# cardV3.net
KiCad netlist of a schematic drawn in EAGLE
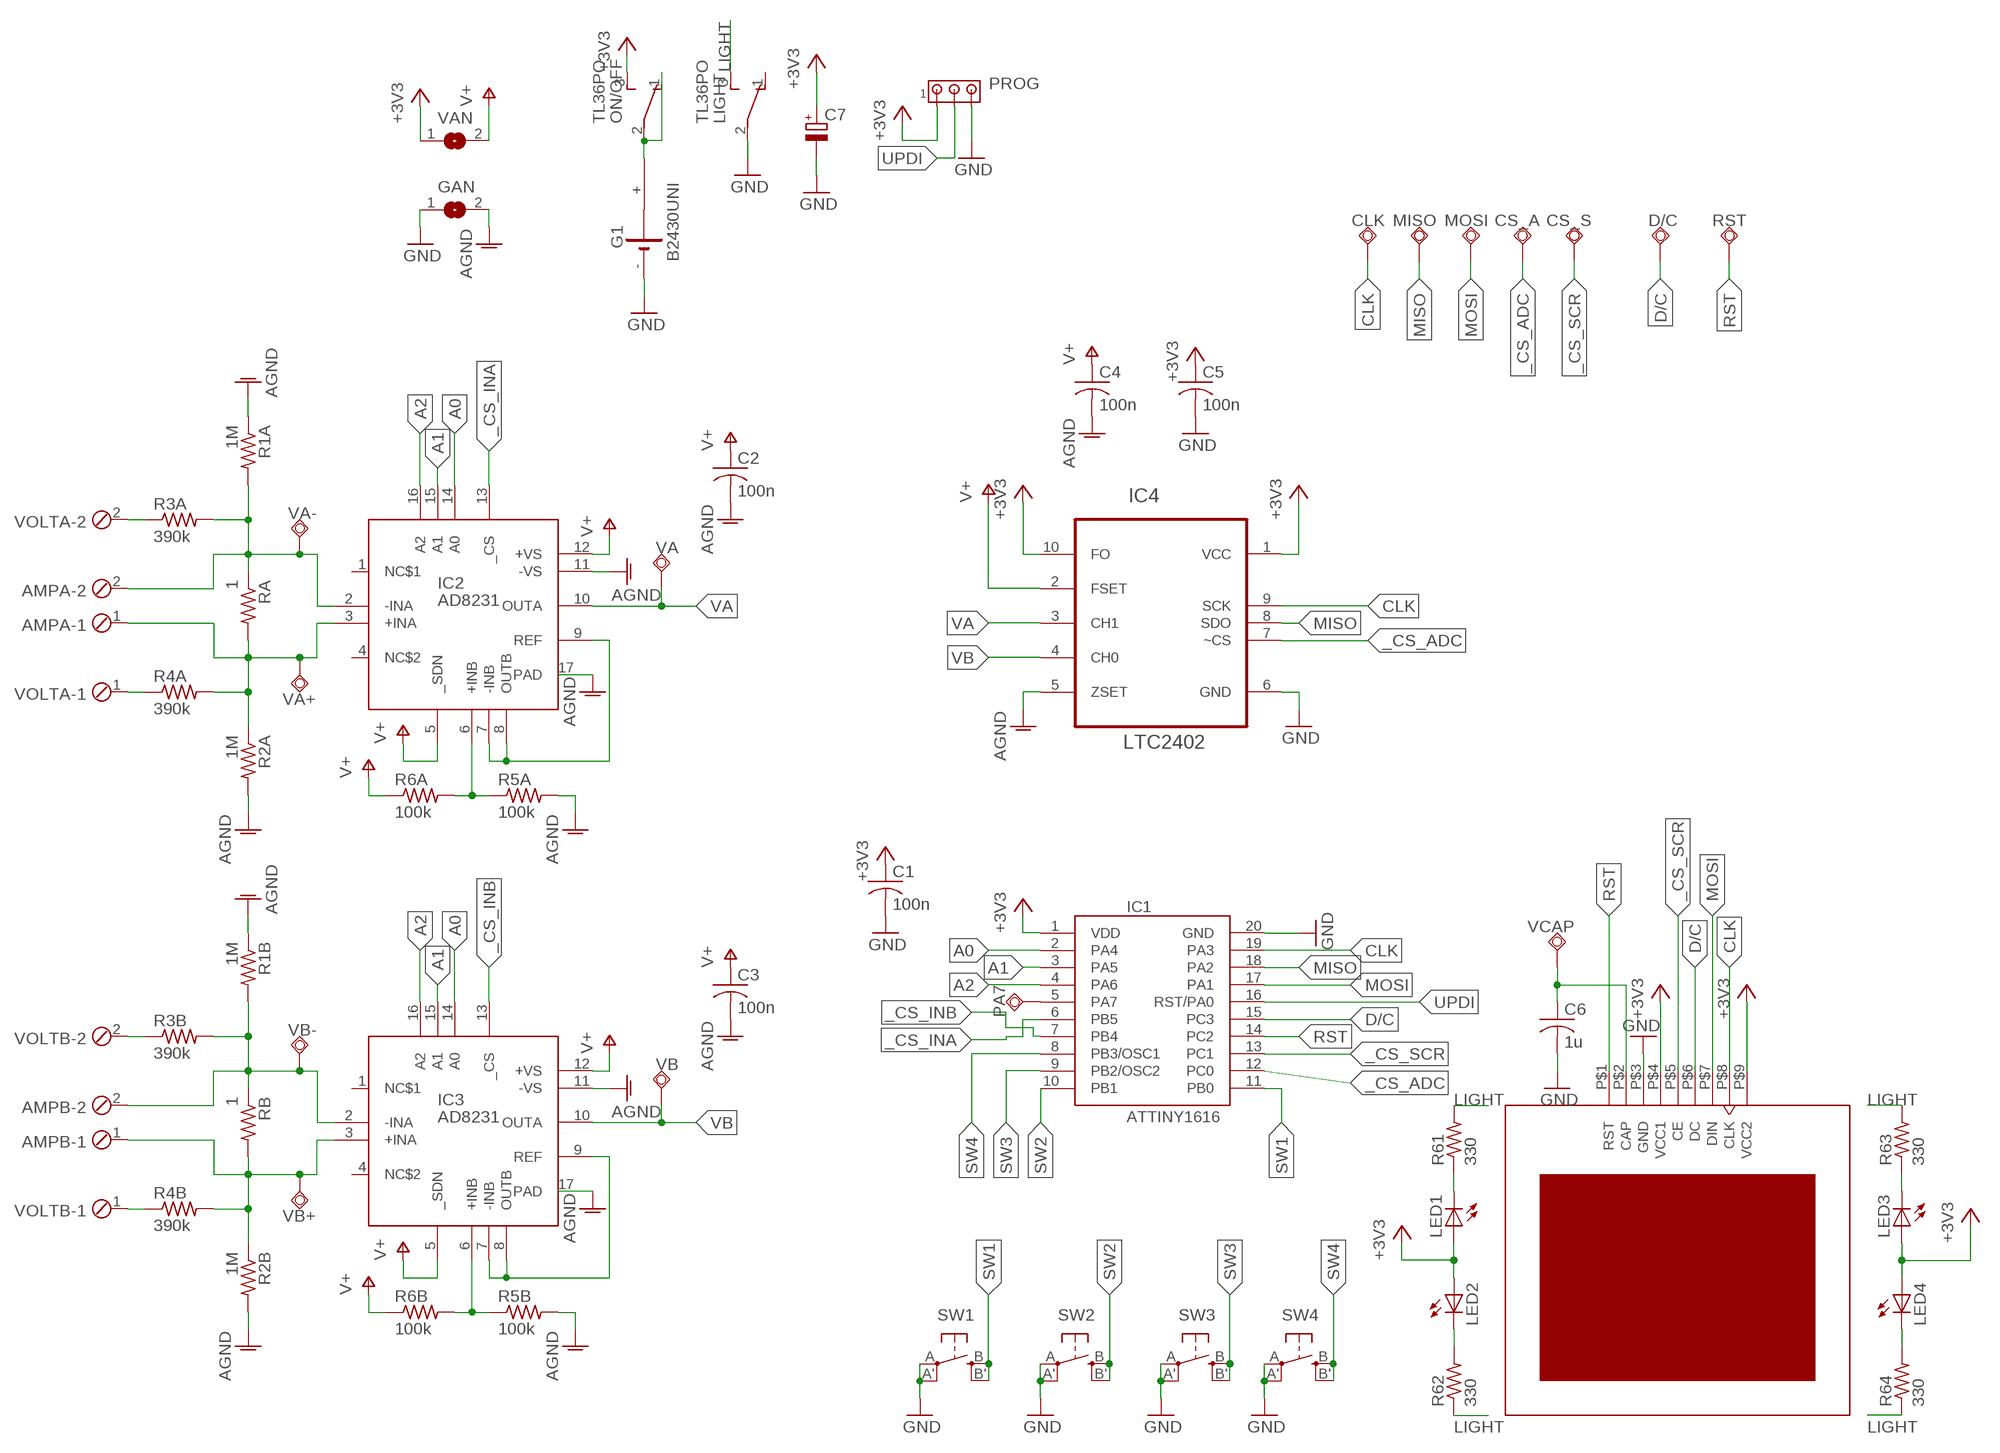
[diagram p0: schematic, sheet 1]

(export (version "E")
  (design (tool "Eeschema 10.0.6"))
  (components
    (comp (ref "AMPA")
      (value "MPT2")
      (footprint "eagle-import:2POL254")
      (libsource (lib "eagle-import") (part "MPT2"))
    )
    (comp (ref "AMPB")
      (value "MPT2")
      (footprint "eagle-import:2POL254")
      (libsource (lib "eagle-import") (part "MPT2"))
    )
    (comp (ref "C1")
      (value "100n")
      (footprint "eagle-import:C0805K")
      (libsource (lib "eagle-import") (part "C-USC0805K"))
    )
    (comp (ref "C2")
      (value "100n")
      (footprint "eagle-import:C0805K")
      (libsource (lib "eagle-import") (part "C-USC0805K"))
    )
    (comp (ref "C3")
      (value "100n")
      (footprint "eagle-import:C0805K")
      (libsource (lib "eagle-import") (part "C-USC0805K"))
    )
    (comp (ref "C4")
      (value "100n")
      (footprint "eagle-import:C0805K")
      (libsource (lib "eagle-import") (part "C-USC0805K"))
    )
    (comp (ref "C5")
      (value "100n")
      (footprint "eagle-import:C0805K")
      (libsource (lib "eagle-import") (part "C-USC0805K"))
    )
    (comp (ref "C6")
      (value "1u")
      (footprint "eagle-import:C0805")
      (libsource (lib "eagle-import") (part "resistor_C-USC0805"))
    )
    (comp (ref "C7")
      (value "CPOL-EU153CLV-0405")
      (footprint "eagle-import:153CLV-0405")
      (libsource (lib "eagle-import") (part "CPOL-EU153CLV-0405"))
    )
    (comp (ref "CLK")
      (value "TPSQB1,27")
      (footprint "eagle-import:B1,27")
      (libsource (lib "eagle-import") (part "TPSQB1,27"))
    )
    (comp (ref "CS_A")
      (value "TPSQB1,27")
      (footprint "eagle-import:B1,27")
      (libsource (lib "eagle-import") (part "TPSQB1,27"))
    )
    (comp (ref "CS_S")
      (value "TPSQB1,27")
      (footprint "eagle-import:B1,27")
      (libsource (lib "eagle-import") (part "TPSQB1,27"))
    )
    (comp (ref "D/C")
      (value "TPSQB1,27")
      (footprint "eagle-import:B1,27")
      (libsource (lib "eagle-import") (part "TPSQB1,27"))
    )
    (comp (ref "G1")
      (value "B2430UNI")
      (footprint "eagle-import:B2430UNI")
      (libsource (lib "eagle-import") (part "B2430UNI"))
    )
    (comp (ref "GAN") (value "SJ") (footprint "eagle-import:SJ") (libsource (lib "eagle-import") (part "SJ")))
    (comp (ref "IC1")
      (value "ATTINY1616")
      (footprint "eagle-import:SO20W")
      (libsource (lib "eagle-import") (part "ATTINY1616"))
    )
    (comp (ref "IC2")
      (value "AD8231")
      (footprint "eagle-import:LFCSP16")
      (libsource (lib "eagle-import") (part "AD8231"))
    )
    (comp (ref "IC3")
      (value "AD8231")
      (footprint "eagle-import:LFCSP16")
      (libsource (lib "eagle-import") (part "AD8231"))
    )
    (comp (ref "IC4")
      (value "LTC2402")
      (footprint "eagle-import:MSOP10")
      (libsource (lib "eagle-import") (part "LTC2402CMS"))
    )
    (comp (ref "LED1")
      (value "LEDCHIP-LED0805")
      (footprint "eagle-import:CHIP-LED0805")
      (libsource (lib "eagle-import") (part "LEDCHIP-LED0805"))
    )
    (comp (ref "LED2")
      (value "LEDCHIP-LED0805")
      (footprint "eagle-import:CHIP-LED0805")
      (libsource (lib "eagle-import") (part "LEDCHIP-LED0805"))
    )
    (comp (ref "LED3")
      (value "LEDCHIP-LED0805")
      (footprint "eagle-import:CHIP-LED0805")
      (libsource (lib "eagle-import") (part "LEDCHIP-LED0805"))
    )
    (comp (ref "LED4")
      (value "LEDCHIP-LED0805")
      (footprint "eagle-import:CHIP-LED0805")
      (libsource (lib "eagle-import") (part "LEDCHIP-LED0805"))
    )
    (comp (ref "LIGHT")
      (value "TL36PO")
      (footprint "eagle-import:TL3XPO")
      (libsource (lib "eagle-import") (part "TL36PO"))
    )
    (comp (ref "MISO")
      (value "TPSQB1,27")
      (footprint "eagle-import:B1,27")
      (libsource (lib "eagle-import") (part "TPSQB1,27"))
    )
    (comp (ref "MOSI")
      (value "TPSQB1,27")
      (footprint "eagle-import:B1,27")
      (libsource (lib "eagle-import") (part "TPSQB1,27"))
    )
    (comp (ref "ON/OFF")
      (value "TL36PO")
      (footprint "eagle-import:TL3XPO")
      (libsource (lib "eagle-import") (part "TL36PO"))
    )
    (comp (ref "PA7")
      (value "TPSQB1,27")
      (footprint "eagle-import:B1,27")
      (libsource (lib "eagle-import") (part "TPSQB1,27"))
    )
    (comp (ref "PROG")
      (value "MTA03-100")
      (footprint "eagle-import:10X03MTA")
      (libsource (lib "eagle-import") (part "MTA03-100"))
    )
    (comp (ref "R1A")
      (value "1M")
      (footprint "eagle-import:M0805")
      (libsource (lib "eagle-import") (part "R-US_M0805"))
    )
    (comp (ref "R1B")
      (value "1M")
      (footprint "eagle-import:M0805")
      (libsource (lib "eagle-import") (part "R-US_M0805"))
    )
    (comp (ref "R2A")
      (value "1M")
      (footprint "eagle-import:M0805")
      (libsource (lib "eagle-import") (part "R-US_M0805"))
    )
    (comp (ref "R2B")
      (value "1M")
      (footprint "eagle-import:M0805")
      (libsource (lib "eagle-import") (part "R-US_M0805"))
    )
    (comp (ref "R3A")
      (value "390k")
      (footprint "eagle-import:M0805")
      (libsource (lib "eagle-import") (part "R-US_M0805"))
    )
    (comp (ref "R3B")
      (value "390k")
      (footprint "eagle-import:M0805")
      (libsource (lib "eagle-import") (part "R-US_M0805"))
    )
    (comp (ref "R4A")
      (value "390k")
      (footprint "eagle-import:M0805")
      (libsource (lib "eagle-import") (part "R-US_M0805"))
    )
    (comp (ref "R4B")
      (value "390k")
      (footprint "eagle-import:M0805")
      (libsource (lib "eagle-import") (part "R-US_M0805"))
    )
    (comp (ref "R5A")
      (value "100k")
      (footprint "eagle-import:M0805")
      (libsource (lib "eagle-import") (part "R-US_M0805"))
    )
    (comp (ref "R5B")
      (value "100k")
      (footprint "eagle-import:M0805")
      (libsource (lib "eagle-import") (part "R-US_M0805"))
    )
    (comp (ref "R6A")
      (value "100k")
      (footprint "eagle-import:M0805")
      (libsource (lib "eagle-import") (part "R-US_M0805"))
    )
    (comp (ref "R6B")
      (value "100k")
      (footprint "eagle-import:M0805")
      (libsource (lib "eagle-import") (part "R-US_M0805"))
    )
    (comp (ref "R61")
      (value "330")
      (footprint "eagle-import:M0805")
      (libsource (lib "eagle-import") (part "R-US_M0805"))
    )
    (comp (ref "R62")
      (value "330")
      (footprint "eagle-import:M0805")
      (libsource (lib "eagle-import") (part "R-US_M0805"))
    )
    (comp (ref "R63")
      (value "330")
      (footprint "eagle-import:M0805")
      (libsource (lib "eagle-import") (part "R-US_M0805"))
    )
    (comp (ref "R64")
      (value "330")
      (footprint "eagle-import:M0805")
      (libsource (lib "eagle-import") (part "R-US_M0805"))
    )
    (comp (ref "RA")
      (value "1")
      (footprint "eagle-import:M0805")
      (libsource (lib "eagle-import") (part "R-US_M0805"))
    )
    (comp (ref "RB")
      (value "1")
      (footprint "eagle-import:M0805")
      (libsource (lib "eagle-import") (part "R-US_M0805"))
    )
    (comp (ref "RST")
      (value "TPSQB1,27")
      (footprint "eagle-import:B1,27")
      (libsource (lib "eagle-import") (part "TPSQB1,27"))
    )
    (comp (ref "SCR")
      (value "NOKIA_SCREEN")
      (footprint "eagle-import:NOKIA_SCREEN")
      (libsource (lib "eagle-import") (part "NOKIA_SCREEN"))
    )
    (comp (ref "SW1")
      (value "SPST_TACT-EVQQ2")
      (footprint "eagle-import:EVQ-Q2")
      (libsource (lib "eagle-import") (part "SPST_TACT-EVQQ2"))
    )
    (comp (ref "SW2")
      (value "SPST_TACT-EVQQ2")
      (footprint "eagle-import:EVQ-Q2")
      (libsource (lib "eagle-import") (part "SPST_TACT-EVQQ2"))
    )
    (comp (ref "SW3")
      (value "SPST_TACT-EVQQ2")
      (footprint "eagle-import:EVQ-Q2")
      (libsource (lib "eagle-import") (part "SPST_TACT-EVQQ2"))
    )
    (comp (ref "SW4")
      (value "SPST_TACT-EVQQ2")
      (footprint "eagle-import:EVQ-Q2")
      (libsource (lib "eagle-import") (part "SPST_TACT-EVQQ2"))
    )
    (comp (ref "VA")
      (value "TPSQB1,27")
      (footprint "eagle-import:B1,27")
      (libsource (lib "eagle-import") (part "TPSQB1,27"))
    )
    (comp (ref "VA+")
      (value "TPSQB1,27")
      (footprint "eagle-import:B1,27")
      (libsource (lib "eagle-import") (part "TPSQB1,27"))
    )
    (comp (ref "VA-")
      (value "TPSQB1,27")
      (footprint "eagle-import:B1,27")
      (libsource (lib "eagle-import") (part "TPSQB1,27"))
    )
    (comp (ref "VAN") (value "SJ") (footprint "eagle-import:SJ") (libsource (lib "eagle-import") (part "SJ")))
    (comp (ref "VB")
      (value "TPSQB1,27")
      (footprint "eagle-import:B1,27")
      (libsource (lib "eagle-import") (part "TPSQB1,27"))
    )
    (comp (ref "VB+")
      (value "TPSQB1,27")
      (footprint "eagle-import:B1,27")
      (libsource (lib "eagle-import") (part "TPSQB1,27"))
    )
    (comp (ref "VB-")
      (value "TPSQB1,27")
      (footprint "eagle-import:B1,27")
      (libsource (lib "eagle-import") (part "TPSQB1,27"))
    )
    (comp (ref "VCAP")
      (value "TPSQB1,27")
      (footprint "eagle-import:B1,27")
      (libsource (lib "eagle-import") (part "TPSQB1,27"))
    )
    (comp (ref "VOLTA")
      (value "MPT2")
      (footprint "eagle-import:2POL254")
      (libsource (lib "eagle-import") (part "MPT2"))
    )
    (comp (ref "VOLTB")
      (value "MPT2")
      (footprint "eagle-import:2POL254")
      (libsource (lib "eagle-import") (part "MPT2"))
    )
  )
  (nets
    (net (code "1") (name "+3V3") (class "Default")
      (node (ref "C1") (pin "1") (pinfunction "1_1") (pintype "passive"))
      (node (ref "C5") (pin "1") (pinfunction "1_1") (pintype "passive"))
      (node (ref "C7") (pin "+") (pinfunction "+_+") (pintype "passive"))
      (node (ref "IC1") (pin "1") (pinfunction "VDD_1") (pintype "power_in"))
      (node (ref "IC4") (pin "1") (pinfunction "VCC_1") (pintype "power_in"))
      (node (ref "IC4") (pin "10") (pinfunction "FO_10") (pintype "input"))
      (node (ref "LED1") (pin "A") (pinfunction "A_A") (pintype "passive"))
      (node (ref "LED2") (pin "A") (pinfunction "A_A") (pintype "passive"))
      (node (ref "LED3") (pin "A") (pinfunction "A_A") (pintype "passive"))
      (node (ref "LED4") (pin "A") (pinfunction "A_A") (pintype "passive"))
      (node (ref "ON/OFF") (pin "3") (pinfunction "S_3") (pintype "passive"))
      (node (ref "PROG") (pin "1") (pinfunction "1_1") (pintype "passive"))
      (node (ref "SCR") (pin "P$4") (pinfunction "VCC1_P$4") (pintype "power_in"))
      (node (ref "SCR") (pin "P$9") (pinfunction "VCC2_P$9") (pintype "power_in"))
      (node (ref "VAN") (pin "1") (pinfunction "1_1") (pintype "passive"))
    )
    (net (code "2") (name "/LIGHT") (class "Default")
      (node (ref "LIGHT") (pin "3") (pinfunction "S_3") (pintype "passive"))
      (node (ref "R61") (pin "2") (pinfunction "2_2") (pintype "passive"))
      (node (ref "R62") (pin "1") (pinfunction "1_1") (pintype "passive"))
      (node (ref "R63") (pin "2") (pinfunction "2_2") (pintype "passive"))
      (node (ref "R64") (pin "1") (pinfunction "1_1") (pintype "passive"))
    )
    (net (code "3") (name "A0") (class "Default")
      (node (ref "IC1") (pin "2") (pinfunction "PA4_2") (pintype "bidirectional"))
      (node (ref "IC2") (pin "14") (pinfunction "A0_14") (pintype "input"))
      (node (ref "IC3") (pin "14") (pinfunction "A0_14") (pintype "input"))
    )
    (net (code "4") (name "A1") (class "Default")
      (node (ref "IC1") (pin "3") (pinfunction "PA5_3") (pintype "bidirectional"))
      (node (ref "IC2") (pin "15") (pinfunction "A1_15") (pintype "input"))
      (node (ref "IC3") (pin "15") (pinfunction "A1_15") (pintype "input"))
    )
    (net (code "5") (name "A2") (class "Default")
      (node (ref "IC1") (pin "4") (pinfunction "PA6_4") (pintype "bidirectional"))
      (node (ref "IC2") (pin "16") (pinfunction "A2_16") (pintype "input"))
      (node (ref "IC3") (pin "16") (pinfunction "A2_16") (pintype "input"))
    )
    (net (code "6") (name "AGND") (class "Default")
      (node (ref "C2") (pin "2") (pinfunction "2_2") (pintype "passive"))
      (node (ref "C3") (pin "2") (pinfunction "2_2") (pintype "passive"))
      (node (ref "C4") (pin "2") (pinfunction "2_2") (pintype "passive"))
      (node (ref "GAN") (pin "2") (pinfunction "2_2") (pintype "passive"))
      (node (ref "IC2") (pin "11") (pinfunction "-VS_11") (pintype "power_in"))
      (node (ref "IC2") (pin "17") (pinfunction "PAD_17") (pintype "power_in"))
      (node (ref "IC3") (pin "11") (pinfunction "-VS_11") (pintype "power_in"))
      (node (ref "IC3") (pin "17") (pinfunction "PAD_17") (pintype "power_in"))
      (node (ref "IC4") (pin "5") (pinfunction "ZSET_5") (pintype "input"))
      (node (ref "R1A") (pin "1") (pinfunction "1_1") (pintype "passive"))
      (node (ref "R1B") (pin "1") (pinfunction "1_1") (pintype "passive"))
      (node (ref "R2A") (pin "2") (pinfunction "2_2") (pintype "passive"))
      (node (ref "R2B") (pin "2") (pinfunction "2_2") (pintype "passive"))
      (node (ref "R5A") (pin "2") (pinfunction "2_2") (pintype "passive"))
      (node (ref "R5B") (pin "2") (pinfunction "2_2") (pintype "passive"))
    )
    (net (code "7") (name "CLK") (class "Default")
      (node (ref "CLK") (pin "TP") (pinfunction "TP_TP") (pintype "input"))
      (node (ref "IC1") (pin "19") (pinfunction "PA3_19") (pintype "bidirectional"))
      (node (ref "IC4") (pin "9") (pinfunction "SCK_9") (pintype "input"))
      (node (ref "SCR") (pin "P$8") (pinfunction "CLK_P$8") (pintype "input"))
    )
    (net (code "8") (name "D{slash}C") (class "Default")
      (node (ref "D/C") (pin "TP") (pinfunction "TP_TP") (pintype "input"))
      (node (ref "IC1") (pin "15") (pinfunction "PC3_15") (pintype "bidirectional"))
      (node (ref "SCR") (pin "P$6") (pinfunction "DC_P$6") (pintype "input"))
    )
    (net (code "9") (name "GND") (class "Default")
      (node (ref "C1") (pin "2") (pinfunction "2_2") (pintype "passive"))
      (node (ref "C5") (pin "2") (pinfunction "2_2") (pintype "passive"))
      (node (ref "C6") (pin "2") (pinfunction "2_2") (pintype "passive"))
      (node (ref "C7") (pin "-") (pinfunction "-_-") (pintype "passive"))
      (node (ref "G1") (pin "-") (pinfunction "-_-") (pintype "passive"))
      (node (ref "GAN") (pin "1") (pinfunction "1_1") (pintype "passive"))
      (node (ref "IC1") (pin "20") (pinfunction "GND_20") (pintype "power_in"))
      (node (ref "IC4") (pin "6") (pinfunction "GND_6") (pintype "passive"))
      (node (ref "LIGHT") (pin "2") (pinfunction "P_2") (pintype "passive"))
      (node (ref "PROG") (pin "3") (pinfunction "3_3") (pintype "passive"))
      (node (ref "SCR") (pin "P$3") (pinfunction "GND_P$3") (pintype "power_in"))
      (node (ref "SW1") (pin "A") (pinfunction "P_A") (pintype "passive"))
      (node (ref "SW1") (pin "A'") (pinfunction "P1_A'") (pintype "passive"))
      (node (ref "SW2") (pin "A") (pinfunction "P_A") (pintype "passive"))
      (node (ref "SW2") (pin "A'") (pinfunction "P1_A'") (pintype "passive"))
      (node (ref "SW3") (pin "A") (pinfunction "P_A") (pintype "passive"))
      (node (ref "SW3") (pin "A'") (pinfunction "P1_A'") (pintype "passive"))
      (node (ref "SW4") (pin "A") (pinfunction "P_A") (pintype "passive"))
      (node (ref "SW4") (pin "A'") (pinfunction "P1_A'") (pintype "passive"))
    )
    (net (code "10") (name "MISO") (class "Default")
      (node (ref "IC1") (pin "18") (pinfunction "PA2_18") (pintype "bidirectional"))
      (node (ref "IC4") (pin "8") (pinfunction "SDO_8") (pintype "output"))
      (node (ref "MISO") (pin "TP") (pinfunction "TP_TP") (pintype "input"))
    )
    (net (code "11") (name "MOSI") (class "Default")
      (node (ref "IC1") (pin "17") (pinfunction "PA1_17") (pintype "bidirectional"))
      (node (ref "MOSI") (pin "TP") (pinfunction "TP_TP") (pintype "input"))
      (node (ref "SCR") (pin "P$7") (pinfunction "DIN_P$7") (pintype "input"))
    )
    (net (code "12") (name "Net-(AMPAB-1)") (class "Default")
      (node (ref "AMPA") (pin "2") (pinfunction "1_2") (pintype "passive"))
      (node (ref "IC2") (pin "2") (pinfunction "-INA_2") (pintype "input"))
      (node (ref "R1A") (pin "2") (pinfunction "2_2") (pintype "passive"))
      (node (ref "R3A") (pin "2") (pinfunction "2_2") (pintype "passive"))
      (node (ref "RA") (pin "1") (pinfunction "1_1") (pintype "passive"))
      (node (ref "VA-") (pin "TP") (pinfunction "TP_TP") (pintype "input"))
    )
    (net (code "13") (name "Net-(AMPBB-1)") (class "Default")
      (node (ref "AMPB") (pin "2") (pinfunction "1_2") (pintype "passive"))
      (node (ref "IC3") (pin "2") (pinfunction "-INA_2") (pintype "input"))
      (node (ref "R1B") (pin "2") (pinfunction "2_2") (pintype "passive"))
      (node (ref "R3B") (pin "2") (pinfunction "2_2") (pintype "passive"))
      (node (ref "RB") (pin "1") (pinfunction "1_1") (pintype "passive"))
      (node (ref "VB-") (pin "TP") (pinfunction "TP_TP") (pintype "input"))
    )
    (net (code "14") (name "Net-(IC1-PA7)") (class "Default")
      (node (ref "IC1") (pin "5") (pinfunction "PA7_5") (pintype "bidirectional"))
      (node (ref "PA7") (pin "TP") (pinfunction "TP_TP") (pintype "input"))
    )
    (net (code "15") (name "Net-(IC2-+INA)") (class "Default")
      (node (ref "AMPA") (pin "1") (pinfunction "1_1") (pintype "passive"))
      (node (ref "IC2") (pin "3") (pinfunction "+INA_3") (pintype "input"))
      (node (ref "R2A") (pin "1") (pinfunction "1_1") (pintype "passive"))
      (node (ref "R4A") (pin "2") (pinfunction "2_2") (pintype "passive"))
      (node (ref "RA") (pin "2") (pinfunction "2_2") (pintype "passive"))
      (node (ref "VA+") (pin "TP") (pinfunction "TP_TP") (pintype "input"))
    )
    (net (code "16") (name "Net-(IC2-+INB)") (class "Default")
      (node (ref "IC2") (pin "6") (pinfunction "+INB_6") (pintype "input"))
      (node (ref "R5A") (pin "1") (pinfunction "1_1") (pintype "passive"))
      (node (ref "R6A") (pin "2") (pinfunction "2_2") (pintype "passive"))
    )
    (net (code "17") (name "Net-(IC2--INB)") (class "Default")
      (node (ref "IC2") (pin "7") (pinfunction "-INB_7") (pintype "input"))
      (node (ref "IC2") (pin "8") (pinfunction "OUTB_8") (pintype "output"))
      (node (ref "IC2") (pin "9") (pinfunction "REF_9") (pintype "input"))
    )
    (net (code "18") (name "Net-(IC3-+INA)") (class "Default")
      (node (ref "AMPB") (pin "1") (pinfunction "1_1") (pintype "passive"))
      (node (ref "IC3") (pin "3") (pinfunction "+INA_3") (pintype "input"))
      (node (ref "R2B") (pin "1") (pinfunction "1_1") (pintype "passive"))
      (node (ref "R4B") (pin "2") (pinfunction "2_2") (pintype "passive"))
      (node (ref "RB") (pin "2") (pinfunction "2_2") (pintype "passive"))
      (node (ref "VB+") (pin "TP") (pinfunction "TP_TP") (pintype "input"))
    )
    (net (code "19") (name "Net-(IC3-+INB)") (class "Default")
      (node (ref "IC3") (pin "6") (pinfunction "+INB_6") (pintype "input"))
      (node (ref "R5B") (pin "1") (pinfunction "1_1") (pintype "passive"))
      (node (ref "R6B") (pin "2") (pinfunction "2_2") (pintype "passive"))
    )
    (net (code "20") (name "Net-(IC3--INB)") (class "Default")
      (node (ref "IC3") (pin "7") (pinfunction "-INB_7") (pintype "input"))
      (node (ref "IC3") (pin "8") (pinfunction "OUTB_8") (pintype "output"))
      (node (ref "IC3") (pin "9") (pinfunction "REF_9") (pintype "input"))
    )
    (net (code "21") (name "Net-(LED1-PadC)") (class "Default")
      (node (ref "LED1") (pin "C") (pinfunction "C_C") (pintype "passive"))
      (node (ref "R61") (pin "1") (pinfunction "1_1") (pintype "passive"))
    )
    (net (code "22") (name "Net-(LED2-PadC)") (class "Default")
      (node (ref "LED2") (pin "C") (pinfunction "C_C") (pintype "passive"))
      (node (ref "R62") (pin "2") (pinfunction "2_2") (pintype "passive"))
    )
    (net (code "23") (name "Net-(LED3-PadC)") (class "Default")
      (node (ref "LED3") (pin "C") (pinfunction "C_C") (pintype "passive"))
      (node (ref "R63") (pin "1") (pinfunction "1_1") (pintype "passive"))
    )
    (net (code "24") (name "Net-(LED4-PadC)") (class "Default")
      (node (ref "LED4") (pin "C") (pinfunction "C_C") (pintype "passive"))
      (node (ref "R64") (pin "2") (pinfunction "2_2") (pintype "passive"))
    )
    (net (code "25") (name "Net-(ON/OFF-O)") (class "Default")
      (node (ref "G1") (pin "+") (pinfunction "+_+") (pintype "passive"))
      (node (ref "ON/OFF") (pin "1") (pinfunction "O_1") (pintype "passive"))
      (node (ref "ON/OFF") (pin "2") (pinfunction "P_2") (pintype "passive"))
    )
    (net (code "26") (name "Net-(R4A-Pad1)") (class "Default")
      (node (ref "R4A") (pin "1") (pinfunction "1_1") (pintype "passive"))
      (node (ref "VOLTA") (pin "1") (pinfunction "1_1") (pintype "passive"))
    )
    (net (code "27") (name "Net-(R4B-Pad1)") (class "Default")
      (node (ref "R4B") (pin "1") (pinfunction "1_1") (pintype "passive"))
      (node (ref "VOLTB") (pin "1") (pinfunction "1_1") (pintype "passive"))
    )
    (net (code "28") (name "Net-(SCR-CAP)") (class "Default")
      (node (ref "C6") (pin "1") (pinfunction "1_1") (pintype "passive"))
      (node (ref "SCR") (pin "P$2") (pinfunction "CAP_P$2") (pintype "passive"))
      (node (ref "VCAP") (pin "TP") (pinfunction "TP_TP") (pintype "input"))
    )
    (net (code "29") (name "Net-(VOLTAB-1)") (class "Default")
      (node (ref "R3A") (pin "1") (pinfunction "1_1") (pintype "passive"))
      (node (ref "VOLTA") (pin "2") (pinfunction "1_2") (pintype "passive"))
    )
    (net (code "30") (name "Net-(VOLTBB-1)") (class "Default")
      (node (ref "R3B") (pin "1") (pinfunction "1_1") (pintype "passive"))
      (node (ref "VOLTB") (pin "2") (pinfunction "1_2") (pintype "passive"))
    )
    (net (code "31") (name "RST") (class "Default")
      (node (ref "IC1") (pin "14") (pinfunction "PC2_14") (pintype "bidirectional"))
      (node (ref "RST") (pin "TP") (pinfunction "TP_TP") (pintype "input"))
      (node (ref "SCR") (pin "P$1") (pinfunction "RST_P$1") (pintype "input"))
    )
    (net (code "32") (name "SW1") (class "Default")
      (node (ref "IC1") (pin "11") (pinfunction "PB0_11") (pintype "bidirectional"))
      (node (ref "SW1") (pin "B") (pinfunction "S_B") (pintype "passive"))
      (node (ref "SW1") (pin "B'") (pinfunction "S1_B'") (pintype "passive"))
    )
    (net (code "33") (name "SW2") (class "Default")
      (node (ref "IC1") (pin "10") (pinfunction "PB1_10") (pintype "bidirectional"))
      (node (ref "SW2") (pin "B") (pinfunction "S_B") (pintype "passive"))
      (node (ref "SW2") (pin "B'") (pinfunction "S1_B'") (pintype "passive"))
    )
    (net (code "34") (name "SW3") (class "Default")
      (node (ref "IC1") (pin "9") (pinfunction "PB2/OSC2_9") (pintype "bidirectional"))
      (node (ref "SW3") (pin "B") (pinfunction "S_B") (pintype "passive"))
      (node (ref "SW3") (pin "B'") (pinfunction "S1_B'") (pintype "passive"))
    )
    (net (code "35") (name "SW4") (class "Default")
      (node (ref "IC1") (pin "8") (pinfunction "PB3/OSC1_8") (pintype "bidirectional"))
      (node (ref "SW4") (pin "B") (pinfunction "S_B") (pintype "passive"))
      (node (ref "SW4") (pin "B'") (pinfunction "S1_B'") (pintype "passive"))
    )
    (net (code "36") (name "UPDI") (class "Default")
      (node (ref "IC1") (pin "16") (pinfunction "RST/PA0_16") (pintype "bidirectional"))
      (node (ref "PROG") (pin "2") (pinfunction "2_2") (pintype "passive"))
    )
    (net (code "37") (name "V+") (class "Default")
      (node (ref "C2") (pin "1") (pinfunction "1_1") (pintype "passive"))
      (node (ref "C3") (pin "1") (pinfunction "1_1") (pintype "passive"))
      (node (ref "C4") (pin "1") (pinfunction "1_1") (pintype "passive"))
      (node (ref "IC2") (pin "12") (pinfunction "+VS_12") (pintype "power_in"))
      (node (ref "IC2") (pin "5") (pinfunction "_SDN_5") (pintype "input"))
      (node (ref "IC3") (pin "12") (pinfunction "+VS_12") (pintype "power_in"))
      (node (ref "IC3") (pin "5") (pinfunction "_SDN_5") (pintype "input"))
      (node (ref "IC4") (pin "2") (pinfunction "FSET_2") (pintype "input"))
      (node (ref "R6A") (pin "1") (pinfunction "1_1") (pintype "passive"))
      (node (ref "R6B") (pin "1") (pinfunction "1_1") (pintype "passive"))
      (node (ref "VAN") (pin "2") (pinfunction "2_2") (pintype "passive"))
    )
    (net (code "38") (name "VA") (class "Default")
      (node (ref "IC2") (pin "10") (pinfunction "OUTA_10") (pintype "output"))
      (node (ref "IC4") (pin "3") (pinfunction "CH1_3") (pintype "input"))
      (node (ref "VA") (pin "TP") (pinfunction "TP_TP") (pintype "input"))
    )
    (net (code "39") (name "VB") (class "Default")
      (node (ref "IC3") (pin "10") (pinfunction "OUTA_10") (pintype "output"))
      (node (ref "IC4") (pin "4") (pinfunction "CH0_4") (pintype "input"))
      (node (ref "VB") (pin "TP") (pinfunction "TP_TP") (pintype "input"))
    )
    (net (code "40") (name "_CS_ADC") (class "Default")
      (node (ref "CS_A") (pin "TP") (pinfunction "TP_TP") (pintype "input"))
      (node (ref "IC1") (pin "12") (pinfunction "PC0_12") (pintype "bidirectional"))
      (node (ref "IC4") (pin "7") (pinfunction "~{CS}_7") (pintype "input"))
    )
    (net (code "41") (name "_CS_INA") (class "Default")
      (node (ref "IC1") (pin "6") (pinfunction "PB5_6") (pintype "bidirectional"))
      (node (ref "IC2") (pin "13") (pinfunction "_CS_13") (pintype "input"))
    )
    (net (code "42") (name "_CS_INB") (class "Default")
      (node (ref "IC1") (pin "7") (pinfunction "PB4_7") (pintype "bidirectional"))
      (node (ref "IC3") (pin "13") (pinfunction "_CS_13") (pintype "input"))
    )
    (net (code "43") (name "_CS_SCR") (class "Default")
      (node (ref "CS_S") (pin "TP") (pinfunction "TP_TP") (pintype "input"))
      (node (ref "IC1") (pin "13") (pinfunction "PC1_13") (pintype "bidirectional"))
      (node (ref "SCR") (pin "P$5") (pinfunction "CE_P$5") (pintype "input"))
    )
    (net (code "44") (name "unconnected-(G1-+-Pad+@1)") (class "Default")
      (node (ref "G1") (pin "+@1") (pinfunction "+_+@1") (pintype "passive"))
    )
    (net (code "45") (name "unconnected-(G1-+-Pad+@2)") (class "Default")
      (node (ref "G1") (pin "+@2") (pinfunction "+_+@2") (pintype "passive"))
    )
    (net (code "46") (name "unconnected-(G1-+-Pad+@3)") (class "Default")
      (node (ref "G1") (pin "+@3") (pinfunction "+_+@3") (pintype "passive"))
    )
    (net (code "47") (name "unconnected-(G1-+-Pad+@4)") (class "Default")
      (node (ref "G1") (pin "+@4") (pinfunction "+_+@4") (pintype "passive"))
    )
    (net (code "48") (name "unconnected-(G1---Pad-@1)") (class "Default")
      (node (ref "G1") (pin "-@1") (pinfunction "-_-@1") (pintype "passive"))
    )
    (net (code "49") (name "unconnected-(IC2-NC$1-Pad1)") (class "Default")
      (node (ref "IC2") (pin "1") (pinfunction "NC$1_1") (pintype "no_connect"))
    )
    (net (code "50") (name "unconnected-(IC2-NC$2-Pad4)") (class "Default")
      (node (ref "IC2") (pin "4") (pinfunction "NC$2_4") (pintype "no_connect"))
    )
    (net (code "51") (name "unconnected-(IC3-NC$1-Pad1)") (class "Default")
      (node (ref "IC3") (pin "1") (pinfunction "NC$1_1") (pintype "no_connect"))
    )
    (net (code "52") (name "unconnected-(IC3-NC$2-Pad4)") (class "Default")
      (node (ref "IC3") (pin "4") (pinfunction "NC$2_4") (pintype "no_connect"))
    )
    (net (code "53") (name "unconnected-(LIGHT-O-Pad1)") (class "Default")
      (node (ref "LIGHT") (pin "1") (pinfunction "O_1") (pintype "passive"))
    )
  )
)
